# MCU.net
KiCad netlist of a schematic drawn in EAGLE
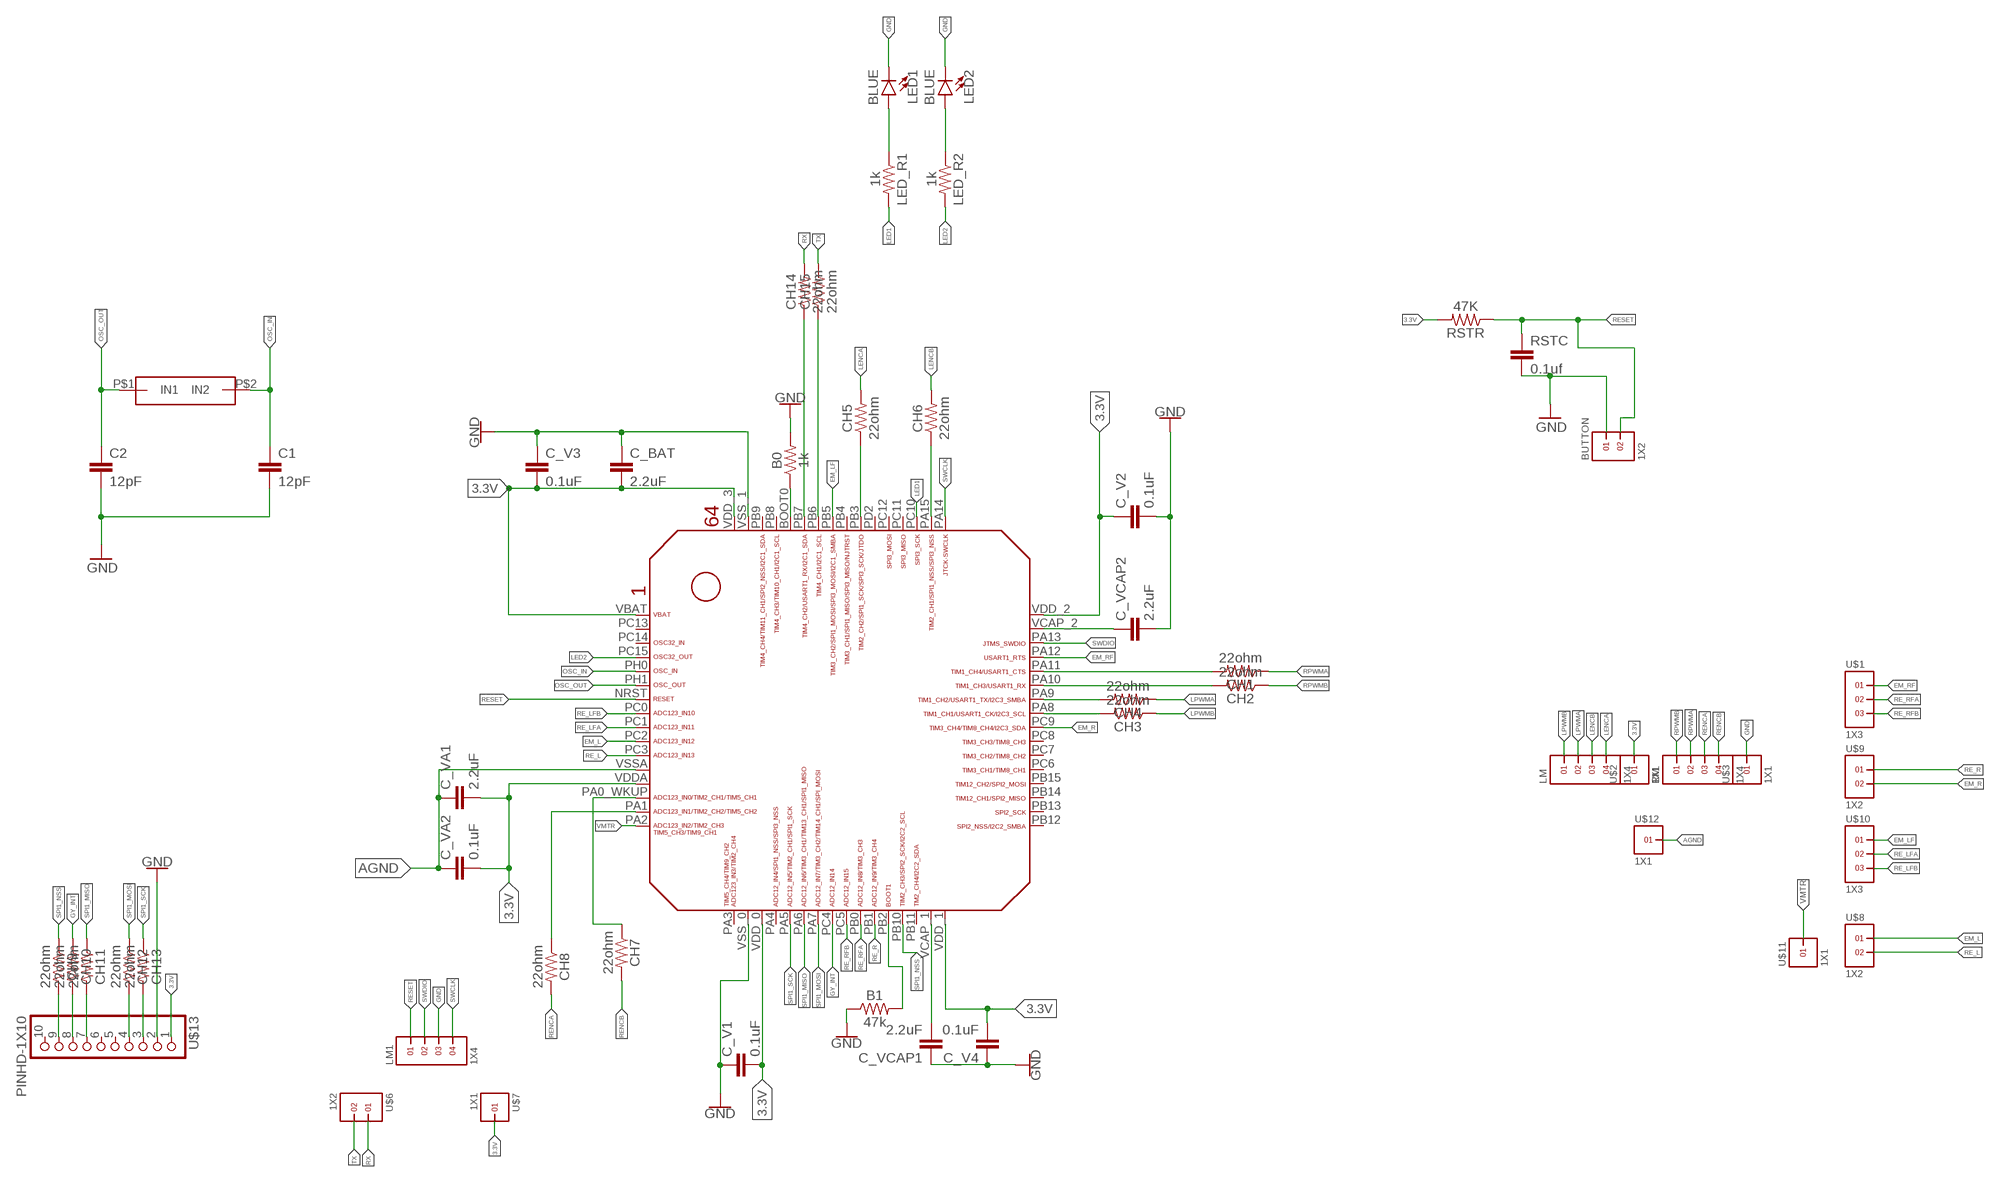
[diagram p0: schematic, sheet 1]

(export (version "E")
  (design (tool "Eeschema 10.0.6"))
  (components
    (comp (ref "B0")
      (value "1k")
      (footprint "eagle-import:0805")
      (libsource (lib "eagle-import") (part "0.75OHM-0805-1/4W-1%"))
    )
    (comp (ref "B1")
      (value "47k")
      (footprint "eagle-import:0805")
      (libsource (lib "eagle-import") (part "0.75OHM-0805-1/4W-1%"))
    )
    (comp (ref "BUTTON")
      (value "1X2")
      (footprint "eagle-import:1X2")
      (libsource (lib "eagle-import") (part "1X2"))
    )
    (comp (ref "C1")
      (value "12pF")
      (footprint "eagle-import:0603")
      (libsource (lib "eagle-import") (part "22PF-0603-50V-5%"))
    )
    (comp (ref "C2")
      (value "12pF")
      (footprint "eagle-import:0603")
      (libsource (lib "eagle-import") (part "22PF-0603-50V-5%"))
    )
    (comp (ref "CH1")
      (value "22ohm")
      (footprint "eagle-import:0805")
      (libsource (lib "eagle-import") (part "0.75OHM-0805-1/4W-1%"))
    )
    (comp (ref "CH2")
      (value "22ohm")
      (footprint "eagle-import:0805")
      (libsource (lib "eagle-import") (part "0.75OHM-0805-1/4W-1%"))
    )
    (comp (ref "CH3")
      (value "22ohm")
      (footprint "eagle-import:0805")
      (libsource (lib "eagle-import") (part "0.75OHM-0805-1/4W-1%"))
    )
    (comp (ref "CH4")
      (value "22ohm")
      (footprint "eagle-import:0805")
      (libsource (lib "eagle-import") (part "0.75OHM-0805-1/4W-1%"))
    )
    (comp (ref "CH5")
      (value "22ohm")
      (footprint "eagle-import:0805")
      (libsource (lib "eagle-import") (part "0.75OHM-0805-1/4W-1%"))
    )
    (comp (ref "CH6")
      (value "22ohm")
      (footprint "eagle-import:0805")
      (libsource (lib "eagle-import") (part "0.75OHM-0805-1/4W-1%"))
    )
    (comp (ref "CH7")
      (value "22ohm")
      (footprint "eagle-import:0805")
      (libsource (lib "eagle-import") (part "0.75OHM-0805-1/4W-1%"))
    )
    (comp (ref "CH8")
      (value "22ohm")
      (footprint "eagle-import:0805")
      (libsource (lib "eagle-import") (part "0.75OHM-0805-1/4W-1%"))
    )
    (comp (ref "CH9")
      (value "22ohm")
      (footprint "eagle-import:0805")
      (libsource (lib "eagle-import") (part "0.75OHM-0805-1/4W-1%"))
    )
    (comp (ref "CH10")
      (value "22ohm")
      (footprint "eagle-import:0805")
      (libsource (lib "eagle-import") (part "0.75OHM-0805-1/4W-1%"))
    )
    (comp (ref "CH11")
      (value "22ohm")
      (footprint "eagle-import:0805")
      (libsource (lib "eagle-import") (part "0.75OHM-0805-1/4W-1%"))
    )
    (comp (ref "CH12")
      (value "22ohm")
      (footprint "eagle-import:0805")
      (libsource (lib "eagle-import") (part "0.75OHM-0805-1/4W-1%"))
    )
    (comp (ref "CH13")
      (value "22ohm")
      (footprint "eagle-import:0805")
      (libsource (lib "eagle-import") (part "0.75OHM-0805-1/4W-1%"))
    )
    (comp (ref "CH14")
      (value "22ohm")
      (footprint "eagle-import:0805")
      (libsource (lib "eagle-import") (part "0.75OHM-0805-1/4W-1%"))
    )
    (comp (ref "CH15")
      (value "22ohm")
      (footprint "eagle-import:0805")
      (libsource (lib "eagle-import") (part "0.75OHM-0805-1/4W-1%"))
    )
    (comp (ref "C_BAT")
      (value "2.2uF")
      (footprint "eagle-import:0805")
      (libsource (lib "eagle-import") (part "22UF-0805-6.3V-20%"))
    )
    (comp (ref "C_V1")
      (value "0.1uF")
      (footprint "eagle-import:0805")
      (libsource (lib "eagle-import") (part "22UF-0805-6.3V-20%"))
    )
    (comp (ref "C_V2")
      (value "0.1uF")
      (footprint "eagle-import:0805")
      (libsource (lib "eagle-import") (part "22UF-0805-6.3V-20%"))
    )
    (comp (ref "C_V3")
      (value "0.1uF")
      (footprint "eagle-import:0805")
      (libsource (lib "eagle-import") (part "22UF-0805-6.3V-20%"))
    )
    (comp (ref "C_V4")
      (value "0.1uF")
      (footprint "eagle-import:0805")
      (libsource (lib "eagle-import") (part "22UF-0805-6.3V-20%"))
    )
    (comp (ref "C_VA1")
      (value "2.2uF")
      (footprint "eagle-import:0805")
      (libsource (lib "eagle-import") (part "22UF-0805-6.3V-20%"))
    )
    (comp (ref "C_VA2")
      (value "0.1uF")
      (footprint "eagle-import:0805")
      (libsource (lib "eagle-import") (part "22UF-0805-6.3V-20%"))
    )
    (comp (ref "C_VCAP1")
      (value "2.2uF")
      (footprint "eagle-import:0805")
      (libsource (lib "eagle-import") (part "22UF-0805-6.3V-20%"))
    )
    (comp (ref "C_VCAP2")
      (value "2.2uF")
      (footprint "eagle-import:0805")
      (libsource (lib "eagle-import") (part "22UF-0805-6.3V-20%"))
    )
    (comp (ref "LED1")
      (value "BLUE")
      (footprint "eagle-import:LED-1206")
      (libsource (lib "eagle-import") (part "LED-BLUE1206"))
    )
    (comp (ref "LED2")
      (value "BLUE")
      (footprint "eagle-import:LED-1206")
      (libsource (lib "eagle-import") (part "LED-BLUE1206"))
    )
    (comp (ref "LED_R1")
      (value "1k")
      (footprint "eagle-import:0805")
      (libsource (lib "eagle-import") (part "0.75OHM-0805-1/4W-1%"))
    )
    (comp (ref "LED_R2")
      (value "1k")
      (footprint "eagle-import:0805")
      (libsource (lib "eagle-import") (part "0.75OHM-0805-1/4W-1%"))
    )
    (comp (ref "LM")
      (value "1X4")
      (footprint "eagle-import:1X4")
      (libsource (lib "eagle-import") (part "1X4"))
    )
    (comp (ref "LM1")
      (value "1X4")
      (footprint "eagle-import:1X4")
      (libsource (lib "eagle-import") (part "1X4"))
    )
    (comp (ref "RM")
      (value "1X4")
      (footprint "eagle-import:1X4")
      (libsource (lib "eagle-import") (part "1X4"))
    )
    (comp (ref "RSTC")
      (value "0.1uf")
      (footprint "eagle-import:0805")
      (libsource (lib "eagle-import") (part "22UF-0805-6.3V-20%"))
    )
    (comp (ref "RSTR")
      (value "47K")
      (footprint "eagle-import:0805")
      (libsource (lib "eagle-import") (part "0.75OHM-0805-1/4W-1%"))
    )
    (comp (ref "U$1")
      (value "1X3")
      (footprint "eagle-import:1X3")
      (libsource (lib "eagle-import") (part "1X3"))
    )
    (comp (ref "U$2")
      (value "1X1")
      (footprint "eagle-import:1X1")
      (libsource (lib "eagle-import") (part "1X1"))
    )
    (comp (ref "U$3")
      (value "1X1")
      (footprint "eagle-import:1X1")
      (libsource (lib "eagle-import") (part "1X1"))
    )
    (comp (ref "U$4")
      (value "STM32F405/415_LQFP64")
      (footprint "eagle-import:STM32F405_415_LQFP64")
      (libsource (lib "eagle-import") (part "STM32F405/415_LQFP64"))
    )
    (comp (ref "U$5")
      (value "OSC")
      (footprint "eagle-import:OSC")
      (libsource (lib "eagle-import") (part "OSC"))
    )
    (comp (ref "U$6")
      (value "1X2")
      (footprint "eagle-import:1X2")
      (libsource (lib "eagle-import") (part "1X2"))
    )
    (comp (ref "U$7")
      (value "1X1")
      (footprint "eagle-import:1X1")
      (libsource (lib "eagle-import") (part "1X1"))
    )
    (comp (ref "U$8")
      (value "1X2")
      (footprint "eagle-import:1X2")
      (libsource (lib "eagle-import") (part "1X2"))
    )
    (comp (ref "U$9")
      (value "1X2")
      (footprint "eagle-import:1X2")
      (libsource (lib "eagle-import") (part "1X2"))
    )
    (comp (ref "U$10")
      (value "1X3")
      (footprint "eagle-import:1X3")
      (libsource (lib "eagle-import") (part "1X3"))
    )
    (comp (ref "U$11")
      (value "1X1")
      (footprint "eagle-import:1X1")
      (libsource (lib "eagle-import") (part "1X1"))
    )
    (comp (ref "U$12")
      (value "1X1")
      (footprint "eagle-import:1X1")
      (libsource (lib "eagle-import") (part "1X1"))
    )
    (comp (ref "U$13")
      (value "PINHD-1X10")
      (footprint "eagle-import:1X10-BIG")
      (libsource (lib "eagle-import") (part "PINHD-1X10"))
    )
  )
  (nets
    (net (code "1") (name "3.3V") (class "Default")
      (node (ref "C_BAT") (pin "2") (pinfunction "2_2") (pintype "passive"))
      (node (ref "C_V1") (pin "2") (pinfunction "2_2") (pintype "passive"))
      (node (ref "C_V2") (pin "1") (pinfunction "1_1") (pintype "passive"))
      (node (ref "C_V3") (pin "2") (pinfunction "2_2") (pintype "passive"))
      (node (ref "C_V4") (pin "2") (pinfunction "2_2") (pintype "passive"))
      (node (ref "C_VA1") (pin "2") (pinfunction "2_2") (pintype "passive"))
      (node (ref "C_VA2") (pin "2") (pinfunction "2_2") (pintype "passive"))
      (node (ref "RSTR") (pin "2") (pinfunction "2_2") (pintype "passive"))
      (node (ref "U$13") (pin "1") (pinfunction "1_1") (pintype "passive"))
      (node (ref "U$2") (pin "1") (pinfunction "1_1") (pintype "bidirectional"))
      (node (ref "U$4") (pin "VBAT") (pinfunction "VBAT_VBAT") (pintype "bidirectional"))
      (node (ref "U$4") (pin "VDDA") (pinfunction "VDDA_VDDA") (pintype "bidirectional"))
      (node (ref "U$4") (pin "VDD_0") (pinfunction "VDD_0_VDD_0") (pintype "bidirectional"))
      (node (ref "U$4") (pin "VDD_1") (pinfunction "VDD_1_VDD_1") (pintype "bidirectional"))
      (node (ref "U$4") (pin "VDD_2") (pinfunction "VDD_2_VDD_2") (pintype "bidirectional"))
      (node (ref "U$4") (pin "VDD_3") (pinfunction "VDD_3_VDD_3") (pintype "bidirectional"))
      (node (ref "U$7") (pin "1") (pinfunction "1_1") (pintype "bidirectional"))
    )
    (net (code "2") (name "AGND") (class "Default")
      (node (ref "C_VA1") (pin "1") (pinfunction "1_1") (pintype "passive"))
      (node (ref "C_VA2") (pin "1") (pinfunction "1_1") (pintype "passive"))
      (node (ref "U$12") (pin "1") (pinfunction "1_1") (pintype "bidirectional"))
      (node (ref "U$4") (pin "VSSA") (pinfunction "VSSA_VSSA") (pintype "bidirectional"))
    )
    (net (code "3") (name "EM_L") (class "Default")
      (node (ref "U$4") (pin "PC2") (pinfunction "PC2_PC2") (pintype "bidirectional"))
      (node (ref "U$8") (pin "1") (pinfunction "1_1") (pintype "bidirectional"))
    )
    (net (code "4") (name "EM_LF") (class "Default")
      (node (ref "U$10") (pin "1") (pinfunction "1_1") (pintype "bidirectional"))
      (node (ref "U$4") (pin "PB5") (pinfunction "PB5_PB5") (pintype "bidirectional"))
    )
    (net (code "5") (name "EM_R") (class "Default")
      (node (ref "U$4") (pin "PC9") (pinfunction "PC9_PC9") (pintype "bidirectional"))
      (node (ref "U$9") (pin "2") (pinfunction "2_2") (pintype "bidirectional"))
    )
    (net (code "6") (name "EM_RF") (class "Default")
      (node (ref "U$1") (pin "1") (pinfunction "1_1") (pintype "bidirectional"))
      (node (ref "U$4") (pin "PA12") (pinfunction "PA12_PA12") (pintype "bidirectional"))
    )
    (net (code "7") (name "GND") (class "Default")
      (node (ref "B0") (pin "2") (pinfunction "2_2") (pintype "passive"))
      (node (ref "B1") (pin "1") (pinfunction "1_1") (pintype "passive"))
      (node (ref "BUTTON") (pin "1") (pinfunction "1_1") (pintype "bidirectional"))
      (node (ref "C1") (pin "2") (pinfunction "2_2") (pintype "passive"))
      (node (ref "C2") (pin "2") (pinfunction "2_2") (pintype "passive"))
      (node (ref "C_BAT") (pin "1") (pinfunction "1_1") (pintype "passive"))
      (node (ref "C_V1") (pin "1") (pinfunction "1_1") (pintype "passive"))
      (node (ref "C_V2") (pin "2") (pinfunction "2_2") (pintype "passive"))
      (node (ref "C_V3") (pin "1") (pinfunction "1_1") (pintype "passive"))
      (node (ref "C_V4") (pin "1") (pinfunction "1_1") (pintype "passive"))
      (node (ref "C_VCAP1") (pin "1") (pinfunction "1_1") (pintype "passive"))
      (node (ref "C_VCAP2") (pin "2") (pinfunction "2_2") (pintype "passive"))
      (node (ref "LED1") (pin "C") (pinfunction "C_C") (pintype "passive"))
      (node (ref "LED2") (pin "C") (pinfunction "C_C") (pintype "passive"))
      (node (ref "LM1") (pin "3") (pinfunction "3_3") (pintype "bidirectional"))
      (node (ref "RSTC") (pin "2") (pinfunction "2_2") (pintype "passive"))
      (node (ref "U$13") (pin "2") (pinfunction "2_2") (pintype "passive"))
      (node (ref "U$3") (pin "1") (pinfunction "1_1") (pintype "bidirectional"))
      (node (ref "U$4") (pin "VSS_0") (pinfunction "VSS_0_VSS_0") (pintype "bidirectional"))
      (node (ref "U$4") (pin "VSS_1") (pinfunction "VSS_1_VSS_1") (pintype "bidirectional"))
    )
    (net (code "8") (name "GY_INT") (class "Default")
      (node (ref "CH10") (pin "1") (pinfunction "1_1") (pintype "passive"))
      (node (ref "U$4") (pin "PC4") (pinfunction "PC4_PC4") (pintype "bidirectional"))
    )
    (net (code "9") (name "LED1") (class "Default")
      (node (ref "LED_R1") (pin "2") (pinfunction "2_2") (pintype "passive"))
      (node (ref "U$4") (pin "PC10") (pinfunction "PC10_PC10") (pintype "bidirectional"))
    )
    (net (code "10") (name "LED2") (class "Default")
      (node (ref "LED_R2") (pin "2") (pinfunction "2_2") (pintype "passive"))
      (node (ref "U$4") (pin "PC15") (pinfunction "PC15_PC15") (pintype "bidirectional"))
    )
    (net (code "11") (name "LENCA") (class "Default")
      (node (ref "CH5") (pin "2") (pinfunction "2_2") (pintype "passive"))
      (node (ref "LM") (pin "4") (pinfunction "4_4") (pintype "bidirectional"))
    )
    (net (code "12") (name "LENCB") (class "Default")
      (node (ref "CH6") (pin "2") (pinfunction "2_2") (pintype "passive"))
      (node (ref "LM") (pin "3") (pinfunction "3_3") (pintype "bidirectional"))
    )
    (net (code "13") (name "LPWMA") (class "Default")
      (node (ref "CH4") (pin "1") (pinfunction "1_1") (pintype "passive"))
      (node (ref "LM") (pin "2") (pinfunction "2_2") (pintype "bidirectional"))
    )
    (net (code "14") (name "LPWMB") (class "Default")
      (node (ref "CH3") (pin "1") (pinfunction "1_1") (pintype "passive"))
      (node (ref "LM") (pin "1") (pinfunction "1_1") (pintype "bidirectional"))
    )
    (net (code "15") (name "Net-(B0-Pad1)") (class "Default")
      (node (ref "B0") (pin "1") (pinfunction "1_1") (pintype "passive"))
      (node (ref "U$4") (pin "BOOT0") (pinfunction "BOOT0_BOOT0") (pintype "bidirectional"))
    )
    (net (code "16") (name "Net-(B1-Pad2)") (class "Default")
      (node (ref "B1") (pin "2") (pinfunction "2_2") (pintype "passive"))
      (node (ref "U$4") (pin "PB2") (pinfunction "PB2_PB2") (pintype "bidirectional"))
    )
    (net (code "17") (name "Net-(CH1-Pad2)") (class "Default")
      (node (ref "CH1") (pin "2") (pinfunction "2_2") (pintype "passive"))
      (node (ref "U$4") (pin "PA11") (pinfunction "PA11_PA11") (pintype "bidirectional"))
    )
    (net (code "18") (name "Net-(CH2-Pad2)") (class "Default")
      (node (ref "CH2") (pin "2") (pinfunction "2_2") (pintype "passive"))
      (node (ref "U$4") (pin "PA10") (pinfunction "PA10_PA10") (pintype "bidirectional"))
    )
    (net (code "19") (name "Net-(CH3-Pad2)") (class "Default")
      (node (ref "CH3") (pin "2") (pinfunction "2_2") (pintype "passive"))
      (node (ref "U$4") (pin "PA8") (pinfunction "PA8_PA8") (pintype "bidirectional"))
    )
    (net (code "20") (name "Net-(CH4-Pad2)") (class "Default")
      (node (ref "CH4") (pin "2") (pinfunction "2_2") (pintype "passive"))
      (node (ref "U$4") (pin "PA9") (pinfunction "PA9_PA9") (pintype "bidirectional"))
    )
    (net (code "21") (name "Net-(CH5-Pad1)") (class "Default")
      (node (ref "CH5") (pin "1") (pinfunction "1_1") (pintype "passive"))
      (node (ref "U$4") (pin "PB3") (pinfunction "PB3_PB3") (pintype "bidirectional"))
    )
    (net (code "22") (name "Net-(CH6-Pad1)") (class "Default")
      (node (ref "CH6") (pin "1") (pinfunction "1_1") (pintype "passive"))
      (node (ref "U$4") (pin "PA15") (pinfunction "PA15_PA15") (pintype "bidirectional"))
    )
    (net (code "23") (name "Net-(CH8-Pad1)") (class "Default")
      (node (ref "CH8") (pin "1") (pinfunction "1_1") (pintype "passive"))
      (node (ref "U$4") (pin "PA1") (pinfunction "PA1_PA1") (pintype "bidirectional"))
    )
    (net (code "24") (name "Net-(CH9-Pad2)") (class "Default")
      (node (ref "CH9") (pin "2") (pinfunction "2_2") (pintype "passive"))
      (node (ref "U$13") (pin "9") (pinfunction "9_9") (pintype "passive"))
    )
    (net (code "25") (name "Net-(CH10-Pad2)") (class "Default")
      (node (ref "CH10") (pin "2") (pinfunction "2_2") (pintype "passive"))
      (node (ref "U$13") (pin "8") (pinfunction "8_8") (pintype "passive"))
    )
    (net (code "26") (name "Net-(CH11-Pad2)") (class "Default")
      (node (ref "CH11") (pin "2") (pinfunction "2_2") (pintype "passive"))
      (node (ref "U$13") (pin "7") (pinfunction "7_7") (pintype "passive"))
    )
    (net (code "27") (name "Net-(CH12-Pad2)") (class "Default")
      (node (ref "CH12") (pin "2") (pinfunction "2_2") (pintype "passive"))
      (node (ref "U$13") (pin "4") (pinfunction "4_4") (pintype "passive"))
    )
    (net (code "28") (name "Net-(CH13-Pad2)") (class "Default")
      (node (ref "CH13") (pin "2") (pinfunction "2_2") (pintype "passive"))
      (node (ref "U$13") (pin "3") (pinfunction "3_3") (pintype "passive"))
    )
    (net (code "29") (name "Net-(CH14-Pad1)") (class "Default")
      (node (ref "CH14") (pin "1") (pinfunction "1_1") (pintype "passive"))
      (node (ref "U$4") (pin "PB7") (pinfunction "PB7_PB7") (pintype "bidirectional"))
    )
    (net (code "30") (name "Net-(CH15-Pad1)") (class "Default")
      (node (ref "CH15") (pin "1") (pinfunction "1_1") (pintype "passive"))
      (node (ref "U$4") (pin "PB6") (pinfunction "PB6_PB6") (pintype "bidirectional"))
    )
    (net (code "31") (name "Net-(C_VCAP1-Pad2)") (class "Default")
      (node (ref "C_VCAP1") (pin "2") (pinfunction "2_2") (pintype "passive"))
      (node (ref "U$4") (pin "VCAP_1") (pinfunction "VCAP_1_VCAP_1") (pintype "bidirectional"))
    )
    (net (code "32") (name "Net-(C_VCAP2-Pad1)") (class "Default")
      (node (ref "C_VCAP2") (pin "1") (pinfunction "1_1") (pintype "passive"))
      (node (ref "U$4") (pin "VCAP_2") (pinfunction "VCAP_2_VCAP_2") (pintype "bidirectional"))
    )
    (net (code "33") (name "Net-(LED1-PadA)") (class "Default")
      (node (ref "LED1") (pin "A") (pinfunction "A_A") (pintype "passive"))
      (node (ref "LED_R1") (pin "1") (pinfunction "1_1") (pintype "passive"))
    )
    (net (code "34") (name "Net-(LED2-PadA)") (class "Default")
      (node (ref "LED2") (pin "A") (pinfunction "A_A") (pintype "passive"))
      (node (ref "LED_R2") (pin "1") (pinfunction "1_1") (pintype "passive"))
    )
    (net (code "35") (name "Net-(U$4-PA0_AKUP)") (class "Default")
      (node (ref "CH7") (pin "1") (pinfunction "1_1") (pintype "passive"))
      (node (ref "U$4") (pin "PA0_WKUP") (pinfunction "PA0_AKUP_PA0_WKUP") (pintype "bidirectional"))
    )
    (net (code "36") (name "OSC_IN") (class "Default")
      (node (ref "C1") (pin "1") (pinfunction "1_1") (pintype "passive"))
      (node (ref "U$4") (pin "PH0") (pinfunction "PH0_PH0") (pintype "bidirectional"))
      (node (ref "U$5") (pin "P$2") (pinfunction "IN2_P$2") (pintype "bidirectional"))
    )
    (net (code "37") (name "OSC_OUT") (class "Default")
      (node (ref "C2") (pin "1") (pinfunction "1_1") (pintype "passive"))
      (node (ref "U$4") (pin "PH1") (pinfunction "PH1_PH1") (pintype "bidirectional"))
      (node (ref "U$5") (pin "P$1") (pinfunction "IN1_P$1") (pintype "bidirectional"))
    )
    (net (code "38") (name "RENCA") (class "Default")
      (node (ref "CH8") (pin "2") (pinfunction "2_2") (pintype "passive"))
      (node (ref "RM") (pin "3") (pinfunction "3_3") (pintype "bidirectional"))
    )
    (net (code "39") (name "RENCB") (class "Default")
      (node (ref "CH7") (pin "2") (pinfunction "2_2") (pintype "passive"))
      (node (ref "RM") (pin "4") (pinfunction "4_4") (pintype "bidirectional"))
    )
    (net (code "40") (name "RESET") (class "Default")
      (node (ref "BUTTON") (pin "2") (pinfunction "2_2") (pintype "bidirectional"))
      (node (ref "LM1") (pin "1") (pinfunction "1_1") (pintype "bidirectional"))
      (node (ref "RSTC") (pin "1") (pinfunction "1_1") (pintype "passive"))
      (node (ref "RSTR") (pin "1") (pinfunction "1_1") (pintype "passive"))
      (node (ref "U$4") (pin "NRST") (pinfunction "NRST_NRST") (pintype "bidirectional"))
    )
    (net (code "41") (name "RE_L") (class "Default")
      (node (ref "U$4") (pin "PC3") (pinfunction "PC3_PC3") (pintype "bidirectional"))
      (node (ref "U$8") (pin "2") (pinfunction "2_2") (pintype "bidirectional"))
    )
    (net (code "42") (name "RE_LFA") (class "Default")
      (node (ref "U$10") (pin "2") (pinfunction "2_2") (pintype "bidirectional"))
      (node (ref "U$4") (pin "PC1") (pinfunction "PC1_PC1") (pintype "bidirectional"))
    )
    (net (code "43") (name "RE_LFB") (class "Default")
      (node (ref "U$10") (pin "3") (pinfunction "3_3") (pintype "bidirectional"))
      (node (ref "U$4") (pin "PC0") (pinfunction "PC0_PC0") (pintype "bidirectional"))
    )
    (net (code "44") (name "RE_R") (class "Default")
      (node (ref "U$4") (pin "PB1") (pinfunction "PB1_PB1") (pintype "bidirectional"))
      (node (ref "U$9") (pin "1") (pinfunction "1_1") (pintype "bidirectional"))
    )
    (net (code "45") (name "RE_RFA") (class "Default")
      (node (ref "U$1") (pin "2") (pinfunction "2_2") (pintype "bidirectional"))
      (node (ref "U$4") (pin "PB0") (pinfunction "PB0_PB0") (pintype "bidirectional"))
    )
    (net (code "46") (name "RE_RFB") (class "Default")
      (node (ref "U$1") (pin "3") (pinfunction "3_3") (pintype "bidirectional"))
      (node (ref "U$4") (pin "PC5") (pinfunction "PC5_PC5") (pintype "bidirectional"))
    )
    (net (code "47") (name "RPWMA") (class "Default")
      (node (ref "CH1") (pin "1") (pinfunction "1_1") (pintype "passive"))
      (node (ref "RM") (pin "2") (pinfunction "2_2") (pintype "bidirectional"))
    )
    (net (code "48") (name "RPWMB") (class "Default")
      (node (ref "CH2") (pin "1") (pinfunction "1_1") (pintype "passive"))
      (node (ref "RM") (pin "1") (pinfunction "1_1") (pintype "bidirectional"))
    )
    (net (code "49") (name "RX") (class "Default")
      (node (ref "CH14") (pin "2") (pinfunction "2_2") (pintype "passive"))
      (node (ref "U$6") (pin "1") (pinfunction "1_1") (pintype "bidirectional"))
    )
    (net (code "50") (name "SPI1_MISO") (class "Default")
      (node (ref "CH11") (pin "1") (pinfunction "1_1") (pintype "passive"))
      (node (ref "U$4") (pin "PA6") (pinfunction "PA6_PA6") (pintype "bidirectional"))
    )
    (net (code "51") (name "SPI1_MOSI") (class "Default")
      (node (ref "CH12") (pin "1") (pinfunction "1_1") (pintype "passive"))
      (node (ref "U$4") (pin "PA7") (pinfunction "PA7_PA7") (pintype "bidirectional"))
    )
    (net (code "52") (name "SPI1_NSS") (class "Default")
      (node (ref "CH9") (pin "1") (pinfunction "1_1") (pintype "passive"))
      (node (ref "U$4") (pin "PB10") (pinfunction "PB10_PB10") (pintype "bidirectional"))
    )
    (net (code "53") (name "SPI1_SCK") (class "Default")
      (node (ref "CH13") (pin "1") (pinfunction "1_1") (pintype "passive"))
      (node (ref "U$4") (pin "PA5") (pinfunction "PA5_PA5") (pintype "bidirectional"))
    )
    (net (code "54") (name "SWCLK") (class "Default")
      (node (ref "LM1") (pin "4") (pinfunction "4_4") (pintype "bidirectional"))
      (node (ref "U$4") (pin "PA14") (pinfunction "PA14_PA14") (pintype "bidirectional"))
    )
    (net (code "55") (name "SWDIO") (class "Default")
      (node (ref "LM1") (pin "2") (pinfunction "2_2") (pintype "bidirectional"))
      (node (ref "U$4") (pin "PA13") (pinfunction "PA13_PA13") (pintype "bidirectional"))
    )
    (net (code "56") (name "TX") (class "Default")
      (node (ref "CH15") (pin "2") (pinfunction "2_2") (pintype "passive"))
      (node (ref "U$6") (pin "2") (pinfunction "2_2") (pintype "bidirectional"))
    )
    (net (code "57") (name "VMTR") (class "Default")
      (node (ref "U$11") (pin "1") (pinfunction "1_1") (pintype "bidirectional"))
      (node (ref "U$4") (pin "PA2") (pinfunction "PA2_PA2") (pintype "bidirectional"))
    )
    (net (code "58") (name "unconnected-(U$4-PadPA3)") (class "Default")
      (node (ref "U$4") (pin "PA3") (pinfunction "PA3_PA3") (pintype "bidirectional"))
    )
    (net (code "59") (name "unconnected-(U$4-PadPA4)") (class "Default")
      (node (ref "U$4") (pin "PA4") (pinfunction "PA4_PA4") (pintype "bidirectional"))
    )
    (net (code "60") (name "unconnected-(U$4-PadPB4)") (class "Default")
      (node (ref "U$4") (pin "PB4") (pinfunction "PB4_PB4") (pintype "bidirectional"))
    )
    (net (code "61") (name "unconnected-(U$4-PadPB8)") (class "Default")
      (node (ref "U$4") (pin "PB8") (pinfunction "PB8_PB8") (pintype "bidirectional"))
    )
    (net (code "62") (name "unconnected-(U$4-PadPB9)") (class "Default")
      (node (ref "U$4") (pin "PB9") (pinfunction "PB9_PB9") (pintype "bidirectional"))
    )
    (net (code "63") (name "unconnected-(U$4-PadPB11)") (class "Default")
      (node (ref "U$4") (pin "PB11") (pinfunction "PB11_PB11") (pintype "bidirectional"))
    )
    (net (code "64") (name "unconnected-(U$4-PadPB12)") (class "Default")
      (node (ref "U$4") (pin "PB12") (pinfunction "PB12_PB12") (pintype "bidirectional"))
    )
    (net (code "65") (name "unconnected-(U$4-PadPB13)") (class "Default")
      (node (ref "U$4") (pin "PB13") (pinfunction "PB13_PB13") (pintype "bidirectional"))
    )
    (net (code "66") (name "unconnected-(U$4-PadPB14)") (class "Default")
      (node (ref "U$4") (pin "PB14") (pinfunction "PB14_PB14") (pintype "bidirectional"))
    )
    (net (code "67") (name "unconnected-(U$4-PadPB15)") (class "Default")
      (node (ref "U$4") (pin "PB15") (pinfunction "PB15_PB15") (pintype "bidirectional"))
    )
    (net (code "68") (name "unconnected-(U$4-PadPC6)") (class "Default")
      (node (ref "U$4") (pin "PC6") (pinfunction "PC6_PC6") (pintype "bidirectional"))
    )
    (net (code "69") (name "unconnected-(U$4-PadPC7)") (class "Default")
      (node (ref "U$4") (pin "PC7") (pinfunction "PC7_PC7") (pintype "bidirectional"))
    )
    (net (code "70") (name "unconnected-(U$4-PadPC8)") (class "Default")
      (node (ref "U$4") (pin "PC8") (pinfunction "PC8_PC8") (pintype "bidirectional"))
    )
    (net (code "71") (name "unconnected-(U$4-PadPC11)") (class "Default")
      (node (ref "U$4") (pin "PC11") (pinfunction "PC11_PC11") (pintype "bidirectional"))
    )
    (net (code "72") (name "unconnected-(U$4-PadPC12)") (class "Default")
      (node (ref "U$4") (pin "PC12") (pinfunction "PC12_PC12") (pintype "bidirectional"))
    )
    (net (code "73") (name "unconnected-(U$4-PadPC13)") (class "Default")
      (node (ref "U$4") (pin "PC13") (pinfunction "PC13_PC13") (pintype "bidirectional"))
    )
    (net (code "74") (name "unconnected-(U$4-PadPC14)") (class "Default")
      (node (ref "U$4") (pin "PC14") (pinfunction "PC14_PC14") (pintype "bidirectional"))
    )
    (net (code "75") (name "unconnected-(U$4-PadPD2)") (class "Default")
      (node (ref "U$4") (pin "PD2") (pinfunction "PD2_PD2") (pintype "bidirectional"))
    )
    (net (code "76") (name "unconnected-(U$13-Pad5)") (class "Default")
      (node (ref "U$13") (pin "5") (pinfunction "5_5") (pintype "passive"))
    )
    (net (code "77") (name "unconnected-(U$13-Pad6)") (class "Default")
      (node (ref "U$13") (pin "6") (pinfunction "6_6") (pintype "passive"))
    )
    (net (code "78") (name "unconnected-(U$13-Pad10)") (class "Default")
      (node (ref "U$13") (pin "10") (pinfunction "10_10") (pintype "passive"))
    )
  )
)
